# Modular_BO.net
KiCad netlist of a schematic drawn in Altium Designer
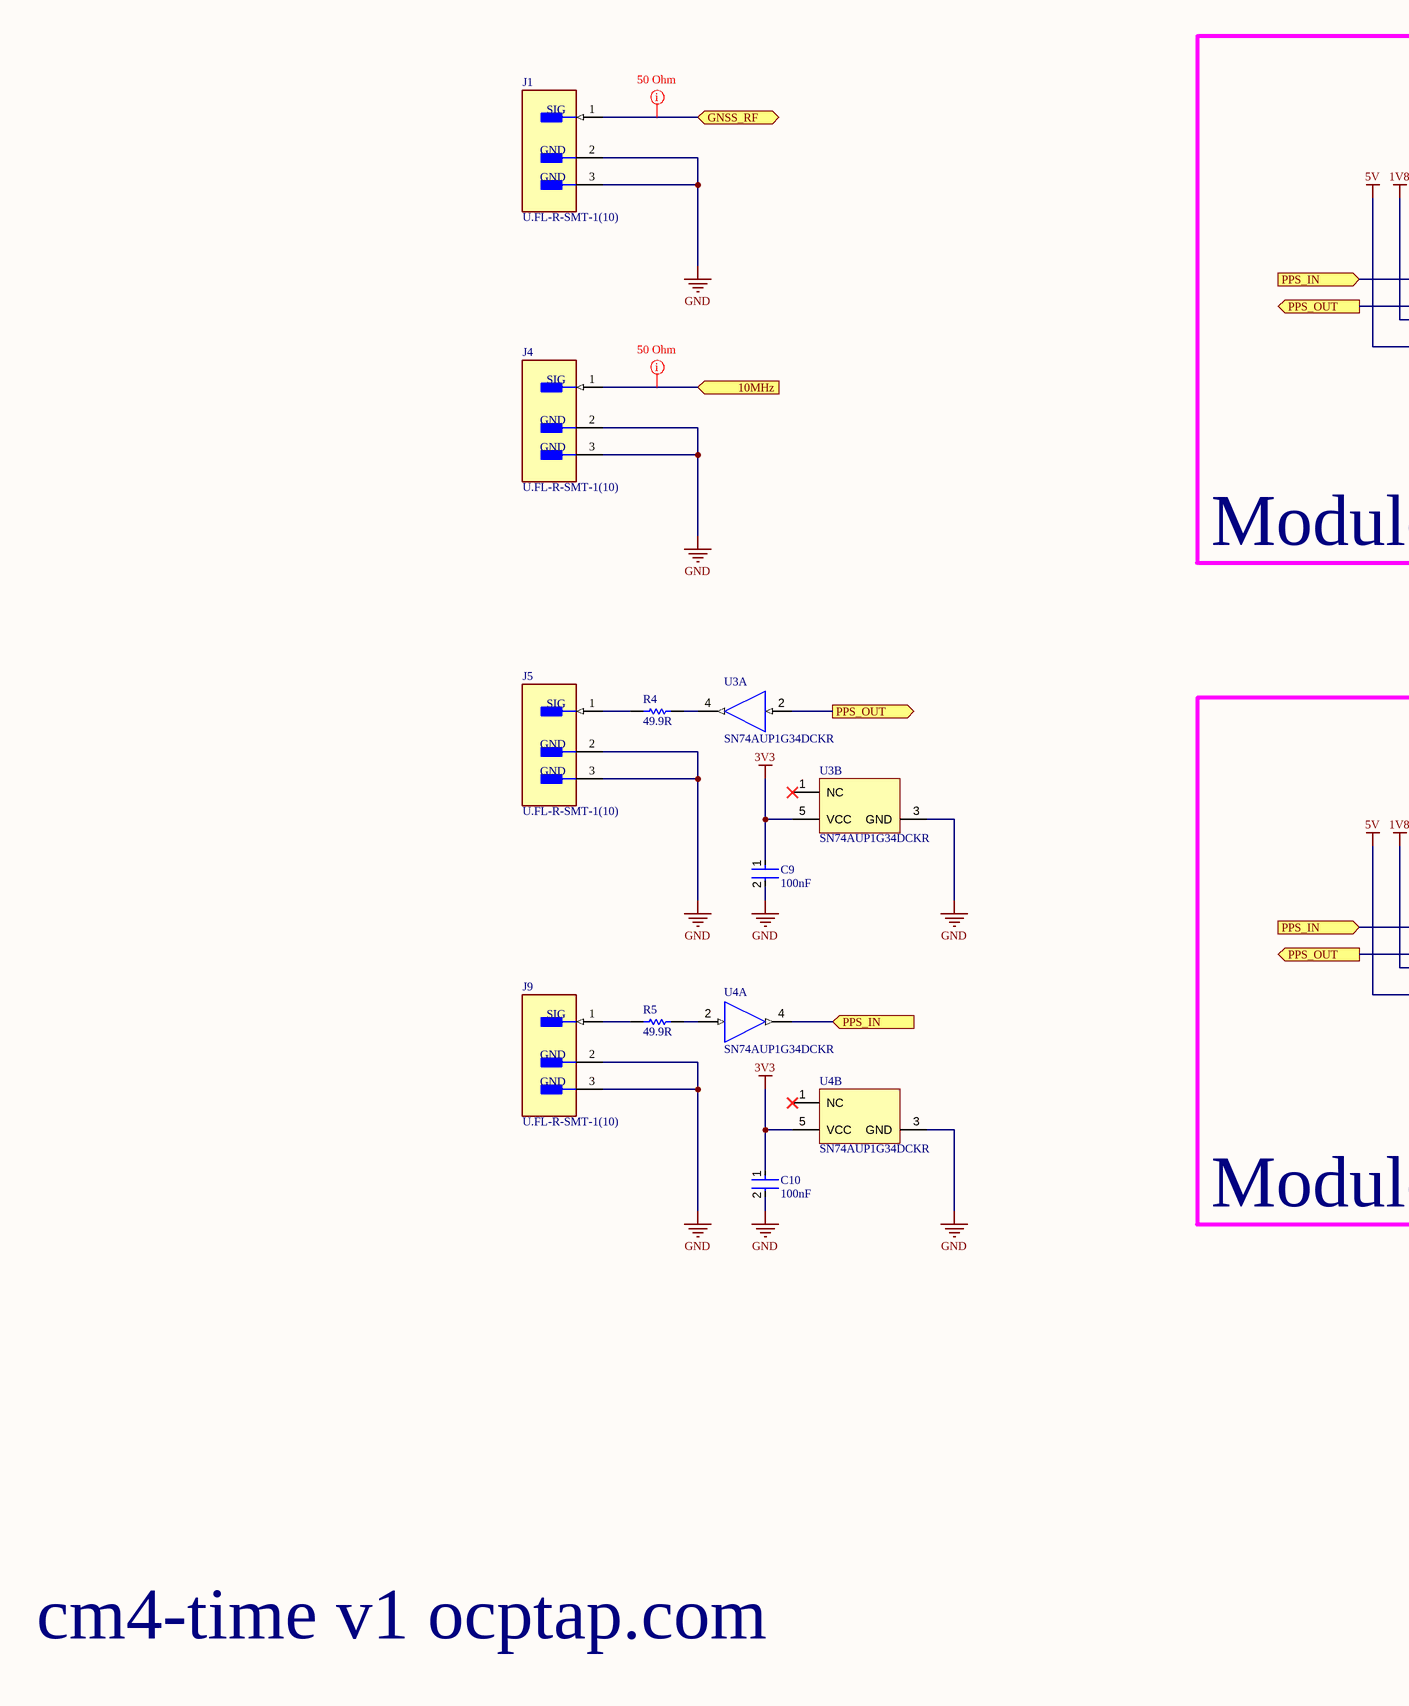
[diagram p0: Modular_BO.SchDoc, left]
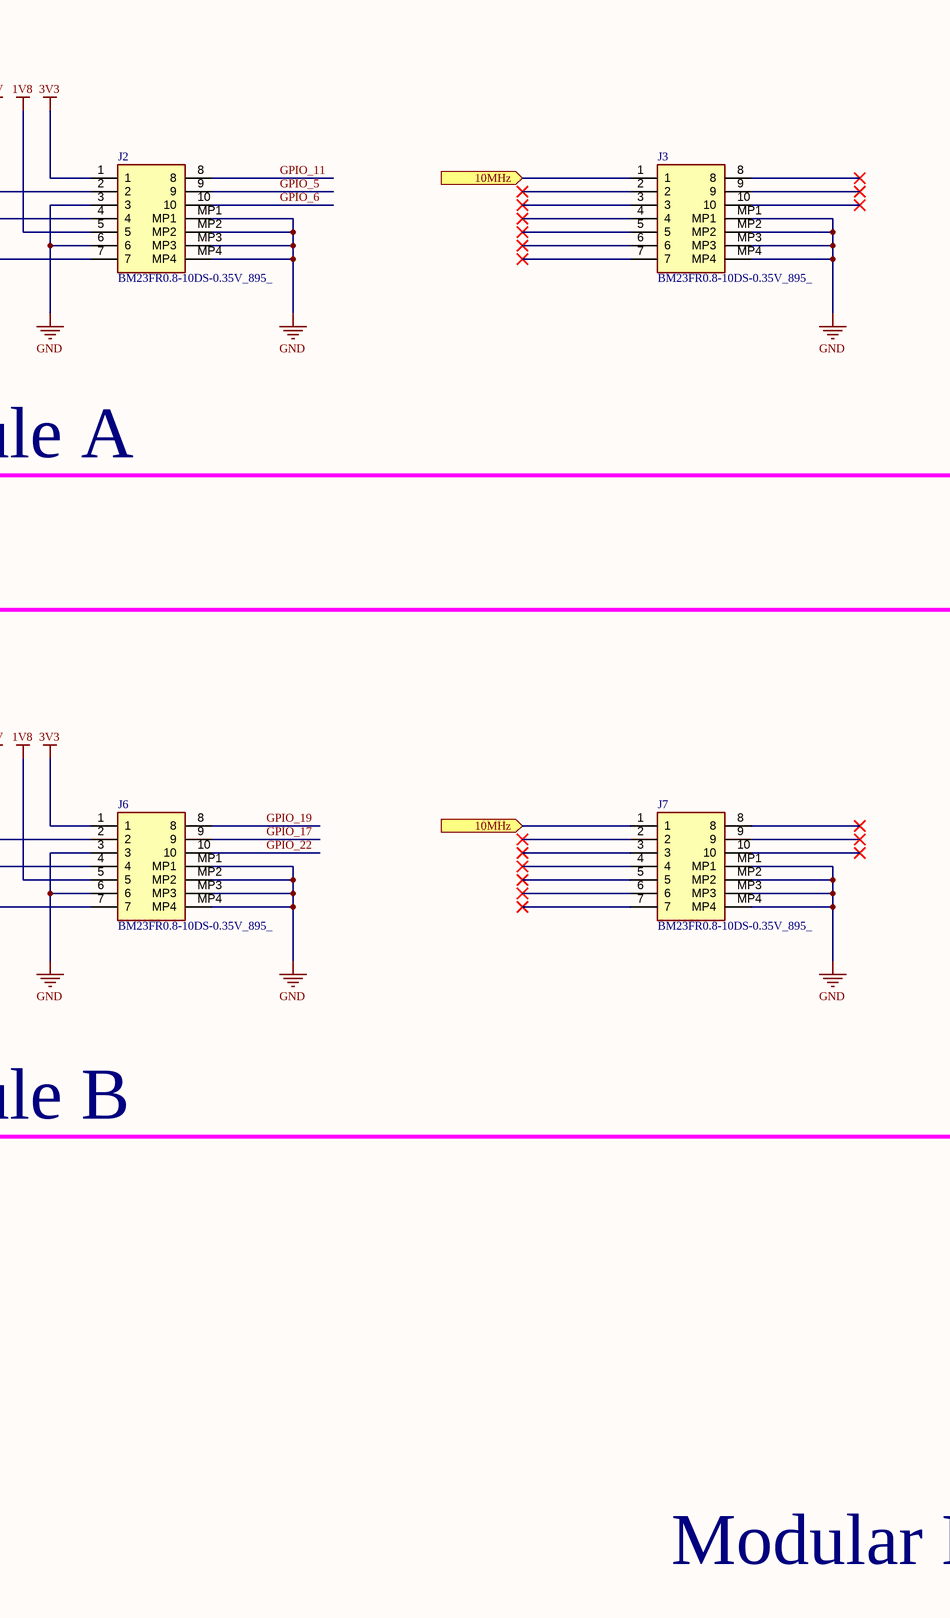
[diagram p1: Modular_BO.SchDoc, right]

(export (version "E")
  (design (tool "Eeschema 10.0.6"))
  (components
    (comp (ref "C9")
      (value "100nF")
      (footprint "FP-C0603C-CF-MFG")
      (description "CAP CER 0.1UF 50V 20% X7R 0603")
      (fields
        (field (name "MANUFACTURER PART NUMBER") "C0603C104M5RACTU")
        (field (name "MANUFACTURER") "KEMET")
      )
      (libsource (lib "Altium Content Vault") (part "b4654b650e69147ec39a6b967a45e02"))
    )
    (comp (ref "C10")
      (value "100nF")
      (footprint "FP-C0603C-CF-MFG")
      (description "CAP CER 0.1UF 50V 20% X7R 0603")
      (fields
        (field (name "MANUFACTURER PART NUMBER") "C0603C104M5RACTU")
        (field (name "MANUFACTURER") "KEMET")
      )
      (libsource (lib "Altium Content Vault") (part "b4654b650e69147ec39a6b967a45e02"))
    )
    (comp (ref "J1")
      (value "U.FL-R-SMT-1(10)")
      (footprint "FP-U_FL-R-SMT-1_10-MFG")
      (description "CONN U.FL RCPT STR 50 OHM SMD")
      (libsource (lib "Altium Content Vault") (part "7158abf7d987fa84906f6fb0d115710"))
    )
    (comp (ref "J2")
      (value "BM23FR0.8-10DS-0.35V_895_")
      (footprint "SamacSys:BM23FR0810DS035V895")
      (description "Connector")
      (fields
        (field (name "MANUFACTURER_PART_NUMBER") "BM23FR0.8-10DS-0.35V(895)")
        (field (name "MOUSER PART NUMBER") "798-3FR0810DS035V895")
      )
      (libsource (lib "*") (part "BM23FR0.8-10DS-0.35V_895_"))
    )
    (comp (ref "J3")
      (value "BM23FR0.8-10DS-0.35V_895_")
      (footprint "SamacSys:BM23FR0810DS035V895")
      (description "Connector")
      (fields
        (field (name "MANUFACTURER_PART_NUMBER") "BM23FR0.8-10DS-0.35V(895)")
        (field (name "MOUSER PART NUMBER") "798-3FR0810DS035V895")
      )
      (libsource (lib "*") (part "BM23FR0.8-10DS-0.35V_895_"))
    )
    (comp (ref "J4")
      (value "U.FL-R-SMT-1(10)")
      (footprint "FP-U_FL-R-SMT-1_10-MFG")
      (description "CONN U.FL RCPT STR 50 OHM SMD")
      (libsource (lib "Altium Content Vault") (part "7158abf7d987fa84906f6fb0d115710"))
    )
    (comp (ref "J5")
      (value "U.FL-R-SMT-1(10)")
      (footprint "FP-U_FL-R-SMT-1_10-MFG")
      (description "CONN U.FL RCPT STR 50 OHM SMD")
      (libsource (lib "Altium Content Vault") (part "7158abf7d987fa84906f6fb0d115710"))
    )
    (comp (ref "J6")
      (value "BM23FR0.8-10DS-0.35V_895_")
      (footprint "SamacSys:BM23FR0810DS035V895")
      (description "Connector")
      (fields
        (field (name "MANUFACTURER_PART_NUMBER") "BM23FR0.8-10DS-0.35V(895)")
        (field (name "MOUSER PART NUMBER") "798-3FR0810DS035V895")
      )
      (libsource (lib "*") (part "BM23FR0.8-10DS-0.35V_895_"))
    )
    (comp (ref "J7")
      (value "BM23FR0.8-10DS-0.35V_895_")
      (footprint "SamacSys:BM23FR0810DS035V895")
      (description "Connector")
      (fields
        (field (name "MANUFACTURER_PART_NUMBER") "BM23FR0.8-10DS-0.35V(895)")
        (field (name "MOUSER PART NUMBER") "798-3FR0810DS035V895")
      )
      (libsource (lib "*") (part "BM23FR0.8-10DS-0.35V_895_"))
    )
    (comp (ref "J9")
      (value "U.FL-R-SMT-1(10)")
      (footprint "FP-U_FL-R-SMT-1_10-MFG")
      (description "CONN U.FL RCPT STR 50 OHM SMD")
      (libsource (lib "Altium Content Vault") (part "7158abf7d987fa84906f6fb0d115710"))
    )
    (comp (ref "R4")
      (value "49.9R")
      (footprint "RESC1608X55X25NL10T15")
      (libsource (lib "Altium Content Vault") (part "RES-2"))
    )
    (comp (ref "R5")
      (value "49.9R")
      (footprint "RESC1608X55X25NL10T15")
      (libsource (lib "Altium Content Vault") (part "RES-2"))
    )
    (comp (ref "U3")
      (value "SN74AUP1G34DCKR")
      (footprint "DCK0005A_M")
      (description "Low-Power Single Buffer Gate, DCK0005A, LARGE T&R")
      (fields
        (field (name "GENERIC PART NUMBER") "SN74AUP1G34")
        (field (name "MANUFACTURER") "Texas Instruments")
      )
      (libsource (lib "Altium Content Vault") (part "TI-SN74XXX1XXX-XX-5"))
    )
    (comp (ref "U4")
      (value "SN74AUP1G34DCKR")
      (footprint "DCK0005A_M")
      (description "Low-Power Single Buffer Gate, DCK0005A, LARGE T&R")
      (fields
        (field (name "GENERIC PART NUMBER") "SN74AUP1G34")
        (field (name "MANUFACTURER") "Texas Instruments")
      )
      (libsource (lib "") (part "TI-SN74XXX1XXX-XX-5_1"))
    )
  )
  (nets
    (net (code "1") (name "/10MHz") (class "Default")
      (node (ref "J3") (pin "1") (pinfunction "1_1") (pintype "passive"))
      (node (ref "J4") (pin "1") (pinfunction "SIG_1") (pintype "input"))
      (node (ref "J7") (pin "1") (pinfunction "1_1") (pintype "passive"))
    )
    (net (code "2") (name "/GNSS_RF") (class "Default")
      (node (ref "J1") (pin "1") (pinfunction "SIG_1") (pintype "input"))
    )
    (net (code "3") (name "/GPIO_5") (class "Default")
      (node (ref "J2") (pin "9") (pinfunction "9_9") (pintype "passive"))
    )
    (net (code "4") (name "/GPIO_6") (class "Default")
      (node (ref "J2") (pin "10") (pinfunction "10_10") (pintype "passive"))
    )
    (net (code "5") (name "/GPIO_11") (class "Default")
      (node (ref "J2") (pin "8") (pinfunction "8_8") (pintype "passive"))
    )
    (net (code "6") (name "/GPIO_17") (class "Default")
      (node (ref "J6") (pin "9") (pinfunction "9_9") (pintype "passive"))
    )
    (net (code "7") (name "/GPIO_19") (class "Default")
      (node (ref "J6") (pin "8") (pinfunction "8_8") (pintype "passive"))
    )
    (net (code "8") (name "/GPIO_22") (class "Default")
      (node (ref "J6") (pin "10") (pinfunction "10_10") (pintype "passive"))
    )
    (net (code "9") (name "/PPS_IN") (class "Default")
      (node (ref "J2") (pin "2") (pinfunction "2_2") (pintype "passive"))
      (node (ref "J6") (pin "2") (pinfunction "2_2") (pintype "passive"))
      (node (ref "U4") (pin "4") (pinfunction "Y_4") (pintype "output"))
    )
    (net (code "10") (name "/PPS_OUT") (class "Default")
      (node (ref "J2") (pin "4") (pinfunction "4_4") (pintype "passive"))
      (node (ref "J6") (pin "4") (pinfunction "4_4") (pintype "passive"))
      (node (ref "U3") (pin "2") (pinfunction "A_2") (pintype "input"))
    )
    (net (code "11") (name "1V8") (class "Default")
      (node (ref "J2") (pin "5") (pinfunction "5_5") (pintype "passive"))
      (node (ref "J6") (pin "5") (pinfunction "5_5") (pintype "passive"))
    )
    (net (code "12") (name "3V3") (class "Default")
      (node (ref "C10") (pin "1") (pinfunction "1_1") (pintype "passive"))
      (node (ref "C9") (pin "1") (pinfunction "1_1") (pintype "passive"))
      (node (ref "J2") (pin "1") (pinfunction "1_1") (pintype "passive"))
      (node (ref "J6") (pin "1") (pinfunction "1_1") (pintype "passive"))
      (node (ref "U3") (pin "5") (pinfunction "VCC_5") (pintype "power_in"))
      (node (ref "U4") (pin "5") (pinfunction "VCC_5") (pintype "power_in"))
    )
    (net (code "13") (name "5V") (class "Default")
      (node (ref "J2") (pin "7") (pinfunction "7_7") (pintype "passive"))
      (node (ref "J6") (pin "7") (pinfunction "7_7") (pintype "passive"))
    )
    (net (code "14") (name "GND") (class "Default")
      (node (ref "C10") (pin "2") (pinfunction "2_2") (pintype "passive"))
      (node (ref "C9") (pin "2") (pinfunction "2_2") (pintype "passive"))
      (node (ref "J1") (pin "2") (pinfunction "GND_2") (pintype "power_in"))
      (node (ref "J1") (pin "3") (pinfunction "GND_3") (pintype "power_in"))
      (node (ref "J2") (pin "3") (pinfunction "3_3") (pintype "passive"))
      (node (ref "J2") (pin "6") (pinfunction "6_6") (pintype "passive"))
      (node (ref "J2") (pin "MP1") (pinfunction "MP1_MP1") (pintype "passive"))
      (node (ref "J2") (pin "MP2") (pinfunction "MP2_MP2") (pintype "passive"))
      (node (ref "J2") (pin "MP3") (pinfunction "MP3_MP3") (pintype "passive"))
      (node (ref "J2") (pin "MP4") (pinfunction "MP4_MP4") (pintype "passive"))
      (node (ref "J3") (pin "MP1") (pinfunction "MP1_MP1") (pintype "passive"))
      (node (ref "J3") (pin "MP2") (pinfunction "MP2_MP2") (pintype "passive"))
      (node (ref "J3") (pin "MP3") (pinfunction "MP3_MP3") (pintype "passive"))
      (node (ref "J3") (pin "MP4") (pinfunction "MP4_MP4") (pintype "passive"))
      (node (ref "J4") (pin "2") (pinfunction "GND_2") (pintype "power_in"))
      (node (ref "J4") (pin "3") (pinfunction "GND_3") (pintype "power_in"))
      (node (ref "J5") (pin "2") (pinfunction "GND_2") (pintype "power_in"))
      (node (ref "J5") (pin "3") (pinfunction "GND_3") (pintype "power_in"))
      (node (ref "J6") (pin "3") (pinfunction "3_3") (pintype "passive"))
      (node (ref "J6") (pin "6") (pinfunction "6_6") (pintype "passive"))
      (node (ref "J6") (pin "MP1") (pinfunction "MP1_MP1") (pintype "passive"))
      (node (ref "J6") (pin "MP2") (pinfunction "MP2_MP2") (pintype "passive"))
      (node (ref "J6") (pin "MP3") (pinfunction "MP3_MP3") (pintype "passive"))
      (node (ref "J6") (pin "MP4") (pinfunction "MP4_MP4") (pintype "passive"))
      (node (ref "J7") (pin "MP1") (pinfunction "MP1_MP1") (pintype "passive"))
      (node (ref "J7") (pin "MP2") (pinfunction "MP2_MP2") (pintype "passive"))
      (node (ref "J7") (pin "MP3") (pinfunction "MP3_MP3") (pintype "passive"))
      (node (ref "J7") (pin "MP4") (pinfunction "MP4_MP4") (pintype "passive"))
      (node (ref "J9") (pin "2") (pinfunction "GND_2") (pintype "power_in"))
      (node (ref "J9") (pin "3") (pinfunction "GND_3") (pintype "power_in"))
      (node (ref "U3") (pin "3") (pinfunction "GND_3") (pintype "power_in"))
      (node (ref "U4") (pin "3") (pinfunction "GND_3") (pintype "power_in"))
    )
    (net (code "15") (name "Net-(J5-SIG)") (class "Default")
      (node (ref "J5") (pin "1") (pinfunction "SIG_1") (pintype "input"))
      (node (ref "R4") (pin "1") (pinfunction "1_1") (pintype "passive"))
    )
    (net (code "16") (name "Net-(J9-SIG)") (class "Default")
      (node (ref "J9") (pin "1") (pinfunction "SIG_1") (pintype "input"))
      (node (ref "R5") (pin "1") (pinfunction "1_1") (pintype "passive"))
    )
    (net (code "17") (name "Net-(U3A-Y)") (class "Default")
      (node (ref "R4") (pin "2") (pinfunction "2_2") (pintype "passive"))
      (node (ref "U3") (pin "4") (pinfunction "Y_4") (pintype "output"))
    )
    (net (code "18") (name "Net-(U4A-A)") (class "Default")
      (node (ref "R5") (pin "2") (pinfunction "2_2") (pintype "passive"))
      (node (ref "U4") (pin "2") (pinfunction "A_2") (pintype "input"))
    )
    (net (code "19") (name "unconnected-(J3-Pad2)") (class "Default")
      (node (ref "J3") (pin "2") (pinfunction "2_2") (pintype "passive+no_connect"))
    )
    (net (code "20") (name "unconnected-(J3-Pad3)") (class "Default")
      (node (ref "J3") (pin "3") (pinfunction "3_3") (pintype "passive+no_connect"))
    )
    (net (code "21") (name "unconnected-(J3-Pad4)") (class "Default")
      (node (ref "J3") (pin "4") (pinfunction "4_4") (pintype "passive+no_connect"))
    )
    (net (code "22") (name "unconnected-(J3-Pad5)") (class "Default")
      (node (ref "J3") (pin "5") (pinfunction "5_5") (pintype "passive+no_connect"))
    )
    (net (code "23") (name "unconnected-(J3-Pad6)") (class "Default")
      (node (ref "J3") (pin "6") (pinfunction "6_6") (pintype "passive+no_connect"))
    )
    (net (code "24") (name "unconnected-(J3-Pad7)") (class "Default")
      (node (ref "J3") (pin "7") (pinfunction "7_7") (pintype "passive+no_connect"))
    )
    (net (code "25") (name "unconnected-(J3-Pad8)") (class "Default")
      (node (ref "J3") (pin "8") (pinfunction "8_8") (pintype "passive+no_connect"))
    )
    (net (code "26") (name "unconnected-(J3-Pad9)") (class "Default")
      (node (ref "J3") (pin "9") (pinfunction "9_9") (pintype "passive+no_connect"))
    )
    (net (code "27") (name "unconnected-(J3-Pad10)") (class "Default")
      (node (ref "J3") (pin "10") (pinfunction "10_10") (pintype "passive+no_connect"))
    )
    (net (code "28") (name "unconnected-(J7-Pad2)") (class "Default")
      (node (ref "J7") (pin "2") (pinfunction "2_2") (pintype "passive+no_connect"))
    )
    (net (code "29") (name "unconnected-(J7-Pad3)") (class "Default")
      (node (ref "J7") (pin "3") (pinfunction "3_3") (pintype "passive+no_connect"))
    )
    (net (code "30") (name "unconnected-(J7-Pad4)") (class "Default")
      (node (ref "J7") (pin "4") (pinfunction "4_4") (pintype "passive+no_connect"))
    )
    (net (code "31") (name "unconnected-(J7-Pad5)") (class "Default")
      (node (ref "J7") (pin "5") (pinfunction "5_5") (pintype "passive+no_connect"))
    )
    (net (code "32") (name "unconnected-(J7-Pad6)") (class "Default")
      (node (ref "J7") (pin "6") (pinfunction "6_6") (pintype "passive+no_connect"))
    )
    (net (code "33") (name "unconnected-(J7-Pad7)") (class "Default")
      (node (ref "J7") (pin "7") (pinfunction "7_7") (pintype "passive+no_connect"))
    )
    (net (code "34") (name "unconnected-(J7-Pad8)") (class "Default")
      (node (ref "J7") (pin "8") (pinfunction "8_8") (pintype "passive+no_connect"))
    )
    (net (code "35") (name "unconnected-(J7-Pad9)") (class "Default")
      (node (ref "J7") (pin "9") (pinfunction "9_9") (pintype "passive+no_connect"))
    )
    (net (code "36") (name "unconnected-(J7-Pad10)") (class "Default")
      (node (ref "J7") (pin "10") (pinfunction "10_10") (pintype "passive+no_connect"))
    )
    (net (code "37") (name "unconnected-(U3B-NC-Pad1)") (class "Default")
      (node (ref "U3") (pin "1") (pinfunction "NC_1") (pintype "passive+no_connect"))
    )
    (net (code "38") (name "unconnected-(U4B-NC-Pad1)") (class "Default")
      (node (ref "U4") (pin "1") (pinfunction "NC_1") (pintype "passive+no_connect"))
    )
  )
)
